# lambda_bl49.net
KiCad netlist of a schematic drawn in EAGLE
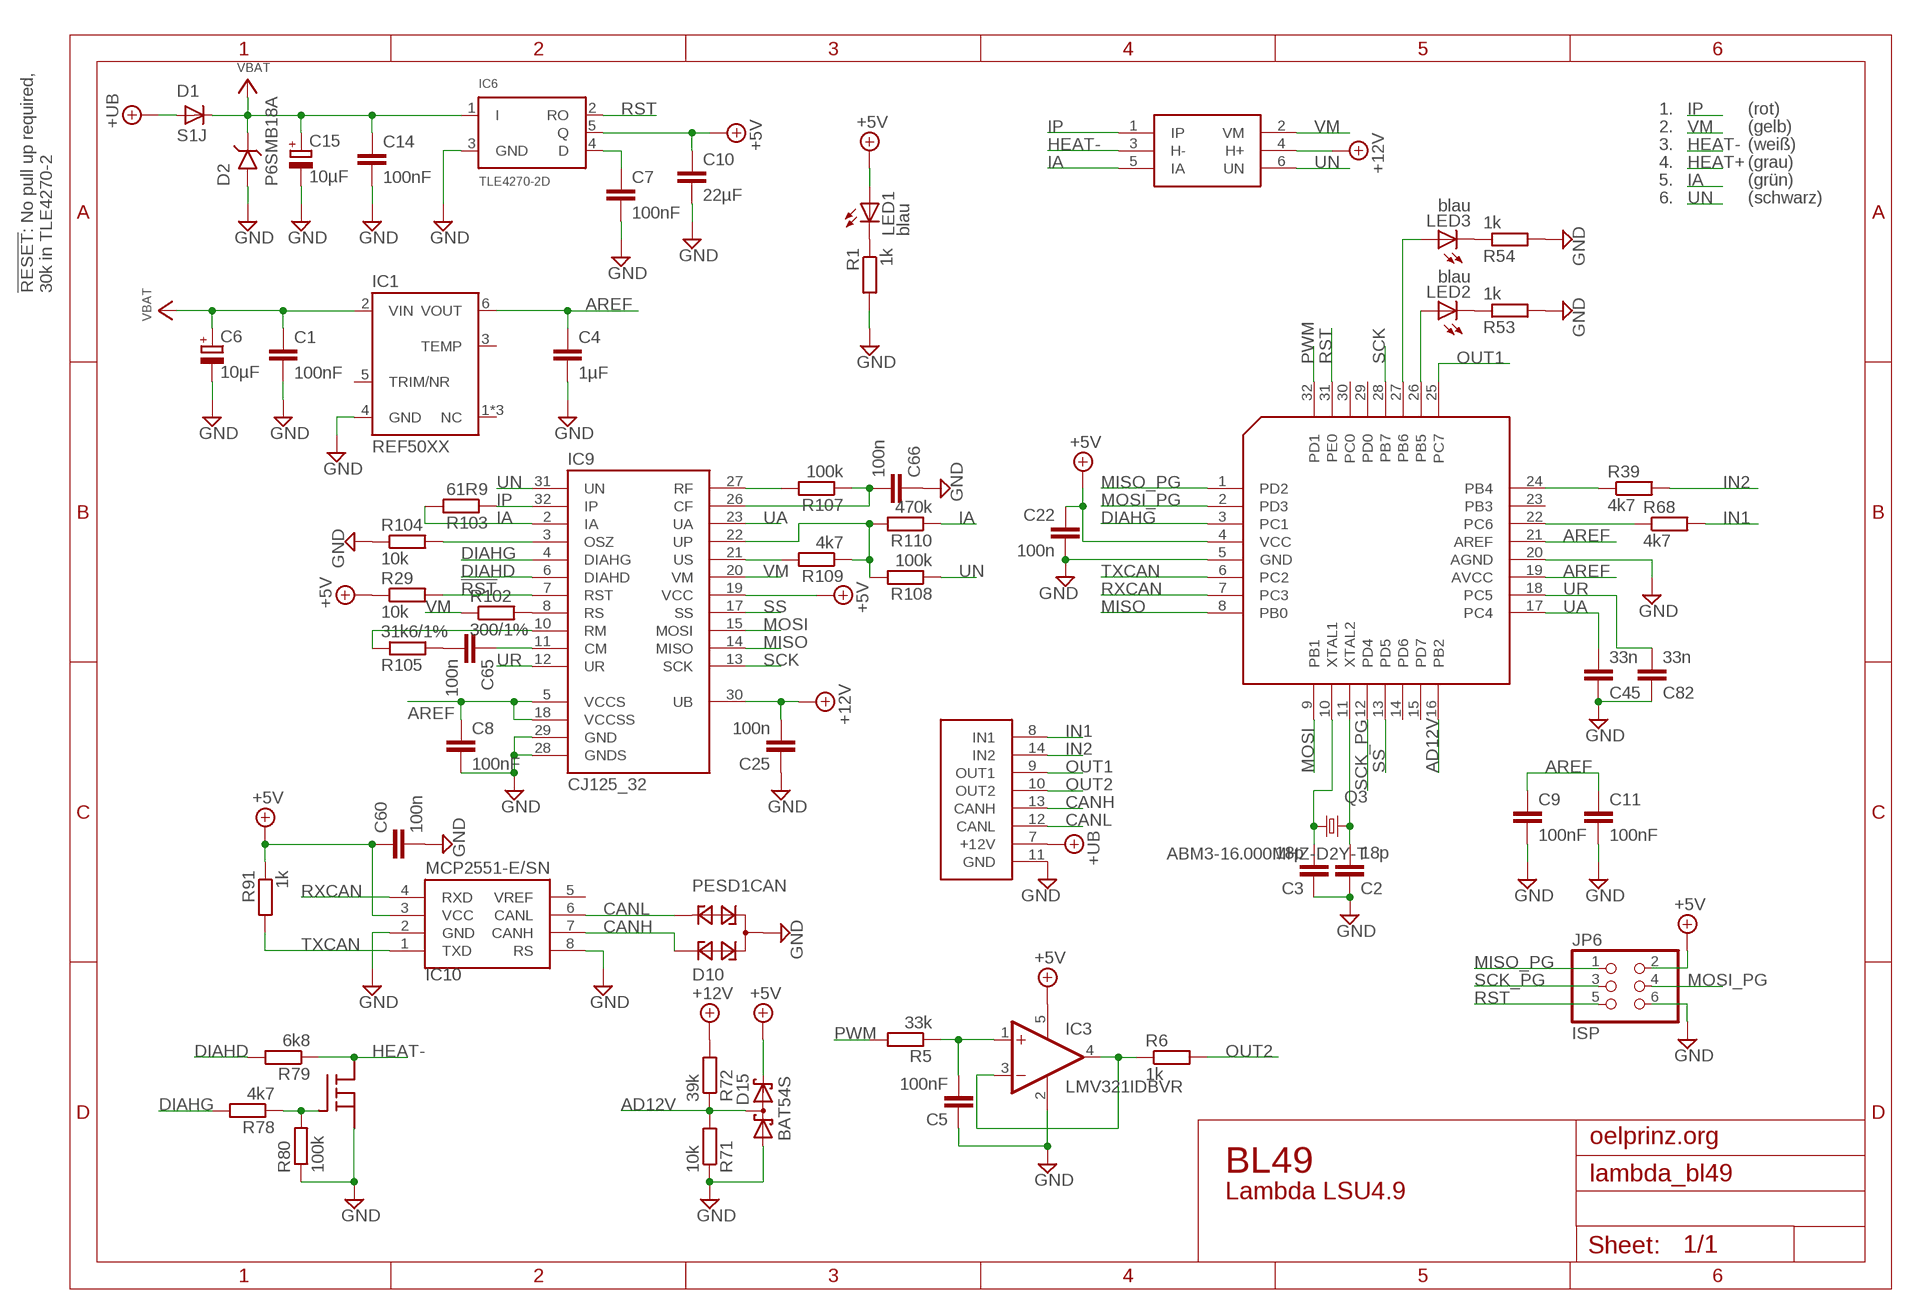
[diagram p0: schematic, sheet 1]

(export (version "E")
  (design (tool "Eeschema 10.0.6"))
  (components
    (comp (ref "C1")
      (value "100nF")
      (footprint "eagle-import:C0603")
      (libsource (lib "eagle-import") (part "rcl_334_C-EUC0603"))
    )
    (comp (ref "C2")
      (value "18p")
      (footprint "eagle-import:C0603")
      (libsource (lib "eagle-import") (part "C-EUC0603"))
    )
    (comp (ref "C3")
      (value "18p")
      (footprint "eagle-import:C0603")
      (libsource (lib "eagle-import") (part "C-EUC0603"))
    )
    (comp (ref "C4")
      (value "1µF")
      (footprint "eagle-import:C0603")
      (libsource (lib "eagle-import") (part "rcl_334_C-EUC0603"))
    )
    (comp (ref "C5")
      (value "100nF")
      (footprint "eagle-import:C0603")
      (libsource (lib "eagle-import") (part "C-EUC0603"))
    )
    (comp (ref "C6")
      (value "10µF")
      (footprint "eagle-import:PANASONIC_D")
      (libsource (lib "eagle-import") (part "CPOL-EUD"))
    )
    (comp (ref "C7")
      (value "100nF")
      (footprint "eagle-import:C0603")
      (libsource (lib "eagle-import") (part "rcl_334_C-EUC0603"))
    )
    (comp (ref "C8")
      (value "100nF")
      (footprint "eagle-import:C0603")
      (libsource (lib "eagle-import") (part "rcl_334_C-EUC0603"))
    )
    (comp (ref "C9")
      (value "100nF")
      (footprint "eagle-import:C0603")
      (libsource (lib "eagle-import") (part "rcl_334_C-EUC0603"))
    )
    (comp (ref "C10")
      (value "22µF")
      (footprint "eagle-import:C1206")
      (libsource (lib "eagle-import") (part "rcl_334_C-EUC1206"))
    )
    (comp (ref "C11")
      (value "100nF")
      (footprint "eagle-import:C0603")
      (libsource (lib "eagle-import") (part "rcl_334_C-EUC0603"))
    )
    (comp (ref "C14")
      (value "100nF")
      (footprint "eagle-import:C0603")
      (libsource (lib "eagle-import") (part "rcl_334_C-EUC0603"))
    )
    (comp (ref "C15")
      (value "10µF")
      (footprint "eagle-import:PANASONIC_D")
      (libsource (lib "eagle-import") (part "CPOL-EUD"))
    )
    (comp (ref "C22")
      (value "100n")
      (footprint "eagle-import:C0603")
      (libsource (lib "eagle-import") (part "C-EUC0603"))
    )
    (comp (ref "C25")
      (value "100n")
      (footprint "eagle-import:C0603")
      (libsource (lib "eagle-import") (part "rcl_334_C-EUC0603"))
    )
    (comp (ref "C45")
      (value "33n")
      (footprint "eagle-import:C0603")
      (libsource (lib "eagle-import") (part "C-EUC0603"))
    )
    (comp (ref "C60")
      (value "100n")
      (footprint "eagle-import:C0603")
      (libsource (lib "eagle-import") (part "C-EUC0603"))
    )
    (comp (ref "C65")
      (value "100n")
      (footprint "eagle-import:C0603")
      (libsource (lib "eagle-import") (part "C-EUC0603"))
    )
    (comp (ref "C66")
      (value "100n")
      (footprint "eagle-import:C0603")
      (libsource (lib "eagle-import") (part "C-EUC0603"))
    )
    (comp (ref "C82")
      (value "33n")
      (footprint "eagle-import:C0603")
      (libsource (lib "eagle-import") (part "C-EUC0603"))
    )
    (comp (ref "D1")
      (value "S1J")
      (footprint "eagle-import:SMADIODE")
      (libsource (lib "eagle-import") (part "DIODESMA"))
    )
    (comp (ref "D2")
      (value "P6SMB18A")
      (footprint "eagle-import:DO-214AA")
      (libsource (lib "eagle-import") (part "P6SMBXXASMB"))
    )
    (comp (ref "D10")
      (value "PESD1CAN")
      (footprint "eagle-import:SOT23")
      (libsource (lib "eagle-import") (part "PESD1CAN"))
    )
    (comp (ref "D15")
      (value "BAT54S")
      (footprint "eagle-import:SOT23")
      (libsource (lib "eagle-import") (part "BAT54S"))
    )
    (comp (ref "IC1")
      (value "REF50XX")
      (footprint "eagle-import:SOIC127P600X175-8N")
      (fields
        (field (name "MANUFACTURER_PART_NUMBER") "REF5050AIDR")
        (field (name "MOUSER_PART_NUMBER") "595-REF5050AIDR")
      )
      (libsource (lib "eagle-import") (part "REF50XX"))
    )
    (comp (ref "IC3")
      (value "LMV321IDBVR")
      (footprint "eagle-import:SC70-5L")
      (libsource (lib "eagle-import") (part "LMV321?M7"))
    )
    (comp (ref "IC6")
      (value "TLE4270-2D")
      (footprint "eagle-import:TO252-51")
      (libsource (lib "eagle-import") (part "TLE4270-2D"))
    )
    (comp (ref "IC9")
      (value "CJ125_32")
      (footprint "eagle-import:TQFP32-08")
      (libsource (lib "eagle-import") (part "CJ125_32"))
    )
    (comp (ref "IC10")
      (value "MCP2551-E/SN")
      (footprint "eagle-import:SOIC8")
      (libsource (lib "eagle-import") (part "MCP255"))
    )
    (comp (ref "JP6")
      (value "ISP")
      (footprint "eagle-import:2X03")
      (libsource (lib "eagle-import") (part "PINHD-2X3"))
    )
    (comp (ref "LED1")
      (value "blau")
      (footprint "eagle-import:SML0805")
      (libsource (lib "eagle-import") (part "LEDSML0805"))
    )
    (comp (ref "LED2")
      (value "blau")
      (footprint "eagle-import:SML0805")
      (libsource (lib "eagle-import") (part "LEDSML0805"))
    )
    (comp (ref "LED3")
      (value "blau")
      (footprint "eagle-import:SML0805")
      (libsource (lib "eagle-import") (part "LEDSML0805"))
    )
    (comp (ref "Q3")
      (value "ABM3-16.000MHZ-D2Y-T")
      (footprint "eagle-import:ABM3")
      (libsource (lib "eagle-import") (part "ABM3-8.000MHZ-D2Y-T"))
    )
    (comp (ref "R1")
      (value "1k")
      (footprint "eagle-import:R0603")
      (libsource (lib "eagle-import") (part "R-EU_R0603"))
    )
    (comp (ref "R5")
      (value "33k")
      (footprint "eagle-import:R0603")
      (libsource (lib "eagle-import") (part "R-EU_R0603"))
    )
    (comp (ref "R6")
      (value "1k")
      (footprint "eagle-import:R0603")
      (libsource (lib "eagle-import") (part "R-EU_R0603"))
    )
    (comp (ref "R29")
      (value "10k")
      (footprint "eagle-import:R0603")
      (libsource (lib "eagle-import") (part "R-EU_R0603"))
    )
    (comp (ref "R39")
      (value "4k7")
      (footprint "eagle-import:R0603")
      (libsource (lib "eagle-import") (part "R-EU_R0603"))
    )
    (comp (ref "R53")
      (value "1k")
      (footprint "eagle-import:R0603")
      (libsource (lib "eagle-import") (part "R-EU_R0603"))
    )
    (comp (ref "R54")
      (value "1k")
      (footprint "eagle-import:R0603")
      (libsource (lib "eagle-import") (part "R-EU_R0603"))
    )
    (comp (ref "R68")
      (value "4k7")
      (footprint "eagle-import:R0603")
      (libsource (lib "eagle-import") (part "R-EU_R0603"))
    )
    (comp (ref "R71")
      (value "10k")
      (footprint "eagle-import:R0603")
      (libsource (lib "eagle-import") (part "R-EU_R0603"))
    )
    (comp (ref "R72")
      (value "39k")
      (footprint "eagle-import:R0603")
      (libsource (lib "eagle-import") (part "R-EU_R0603"))
    )
    (comp (ref "R78")
      (value "4k7")
      (footprint "eagle-import:R0603")
      (libsource (lib "eagle-import") (part "R-EU_R0603"))
    )
    (comp (ref "R79")
      (value "6k8")
      (footprint "eagle-import:R0603")
      (libsource (lib "eagle-import") (part "R-EU_R0603"))
    )
    (comp (ref "R80")
      (value "100k")
      (footprint "eagle-import:R0603")
      (libsource (lib "eagle-import") (part "R-EU_R0603"))
    )
    (comp (ref "R91")
      (value "1k")
      (footprint "eagle-import:R0603")
      (libsource (lib "eagle-import") (part "R-EU_R0603"))
    )
    (comp (ref "R102")
      (value "300/1%")
      (footprint "eagle-import:R0603")
      (libsource (lib "eagle-import") (part "R-EU_R0603"))
    )
    (comp (ref "R103")
      (value "61R9")
      (footprint "eagle-import:R0603")
      (libsource (lib "eagle-import") (part "R-EU_R0603"))
    )
    (comp (ref "R104")
      (value "10k")
      (footprint "eagle-import:R0603")
      (libsource (lib "eagle-import") (part "R-EU_R0603"))
    )
    (comp (ref "R105")
      (value "31k6/1%")
      (footprint "eagle-import:R0603")
      (libsource (lib "eagle-import") (part "R-EU_R0603"))
    )
    (comp (ref "R107")
      (value "100k")
      (footprint "eagle-import:R0603")
      (libsource (lib "eagle-import") (part "R-EU_R0603"))
    )
    (comp (ref "R108")
      (value "100k")
      (footprint "eagle-import:R0603")
      (libsource (lib "eagle-import") (part "R-EU_R0603"))
    )
    (comp (ref "R109")
      (value "4k7")
      (footprint "eagle-import:R0603")
      (libsource (lib "eagle-import") (part "R-EU_R0603"))
    )
    (comp (ref "R110")
      (value "470k")
      (footprint "eagle-import:R0603")
      (libsource (lib "eagle-import") (part "R-EU_R0603"))
    )
    (comp (ref "U$1")
      (value "BL49")
      (footprint "eagle-import:BL49")
      (libsource (lib "eagle-import") (part "BL49"))
    )
    (comp (ref "U$2")
      (value "ATMEGA32M1-AU")
      (footprint "eagle-import:TQFP32-08")
      (libsource (lib "eagle-import") (part "AT32M1"))
    )
    (comp (ref "U$3")
      (value "STD30NF06LT4")
      (footprint "eagle-import:DPACK_2")
      (libsource (lib "eagle-import") (part "IRLZ44"))
    )
  )
  (nets
    (net (code "1") (name "+5V") (class "Default")
      (node (ref "C10") (pin "1") (pinfunction "1_1") (pintype "passive"))
      (node (ref "C22") (pin "1") (pinfunction "1_1") (pintype "passive"))
      (node (ref "C60") (pin "1") (pinfunction "1_1") (pintype "passive"))
      (node (ref "D15") (pin "2") (pinfunction "C2_2") (pintype "passive"))
      (node (ref "IC10") (pin "3") (pinfunction "VCC_3") (pintype "bidirectional"))
      (node (ref "IC3") (pin "5") (pinfunction "V+_5") (pintype "power_in"))
      (node (ref "IC6") (pin "5") (pinfunction "Q_5") (pintype "bidirectional"))
      (node (ref "IC9") (pin "19") (pinfunction "VCC_19") (pintype "bidirectional"))
      (node (ref "JP6") (pin "2") (pinfunction "2_2") (pintype "passive"))
      (node (ref "LED1") (pin "A") (pinfunction "A_A") (pintype "passive"))
      (node (ref "R29") (pin "1") (pinfunction "1_1") (pintype "passive"))
      (node (ref "R91") (pin "1") (pinfunction "1_1") (pintype "passive"))
      (node (ref "U$2") (pin "4") (pinfunction "VCC_4") (pintype "bidirectional"))
    )
    (net (code "2") (name "+12V") (class "Default")
      (node (ref "C25") (pin "2") (pinfunction "2_2") (pintype "passive"))
      (node (ref "IC9") (pin "30") (pinfunction "UB_30") (pintype "bidirectional"))
      (node (ref "R72") (pin "2") (pinfunction "2_2") (pintype "passive"))
      (node (ref "U$1") (pin "4") (pinfunction "H+_4") (pintype "bidirectional"))
    )
    (net (code "3") (name "+UB") (class "Default")
      (node (ref "D1") (pin "A") (pinfunction "A_A") (pintype "passive"))
      (node (ref "U$1") (pin "7") (pinfunction "+12V_7") (pintype "bidirectional"))
    )
    (net (code "4") (name "/AD12V") (class "Default")
      (node (ref "D15") (pin "3") (pinfunction "C1A2_3") (pintype "passive"))
      (node (ref "R71") (pin "2") (pinfunction "2_2") (pintype "passive"))
      (node (ref "R72") (pin "1") (pinfunction "1_1") (pintype "passive"))
      (node (ref "U$2") (pin "16") (pinfunction "PB2_16") (pintype "bidirectional"))
    )
    (net (code "5") (name "/AREF") (class "Default")
      (node (ref "C11") (pin "1") (pinfunction "1_1") (pintype "passive"))
      (node (ref "C4") (pin "1") (pinfunction "1_1") (pintype "passive"))
      (node (ref "C8") (pin "1") (pinfunction "1_1") (pintype "passive"))
      (node (ref "C9") (pin "1") (pinfunction "1_1") (pintype "passive"))
      (node (ref "IC1") (pin "6") (pinfunction "VOUT_6") (pintype "output"))
      (node (ref "IC9") (pin "18") (pinfunction "VCCSS_18") (pintype "bidirectional"))
      (node (ref "IC9") (pin "5") (pinfunction "VCCS_5") (pintype "bidirectional"))
      (node (ref "U$2") (pin "19") (pinfunction "AVCC_19") (pintype "bidirectional"))
      (node (ref "U$2") (pin "21") (pinfunction "AREF_21") (pintype "bidirectional"))
    )
    (net (code "6") (name "/CANH") (class "Default")
      (node (ref "D10") (pin "1") (pinfunction "1_1") (pintype "passive"))
      (node (ref "IC10") (pin "7") (pinfunction "CANH_7") (pintype "bidirectional"))
      (node (ref "U$1") (pin "13") (pinfunction "CANH_13") (pintype "bidirectional"))
    )
    (net (code "7") (name "/CANL") (class "Default")
      (node (ref "D10") (pin "2") (pinfunction "2_2") (pintype "passive"))
      (node (ref "IC10") (pin "6") (pinfunction "CANL_6") (pintype "bidirectional"))
      (node (ref "U$1") (pin "12") (pinfunction "CANL_12") (pintype "bidirectional"))
    )
    (net (code "8") (name "/DIAHD") (class "Default")
      (node (ref "IC9") (pin "6") (pinfunction "DIAHD_6") (pintype "bidirectional"))
      (node (ref "R79") (pin "2") (pinfunction "2_2") (pintype "passive"))
    )
    (net (code "9") (name "/DIAHG") (class "Default")
      (node (ref "IC9") (pin "4") (pinfunction "DIAHG_4") (pintype "bidirectional"))
      (node (ref "R78") (pin "2") (pinfunction "2_2") (pintype "passive"))
      (node (ref "U$2") (pin "3") (pinfunction "PC1_3") (pintype "bidirectional"))
    )
    (net (code "11") (name "/HEAT-") (class "Default")
      (node (ref "R79") (pin "1") (pinfunction "1_1") (pintype "passive"))
      (node (ref "U$1") (pin "3") (pinfunction "H-_3") (pintype "bidirectional"))
      (node (ref "U$3") (pin "D") (pinfunction "2_D") (pintype "bidirectional"))
    )
    (net (code "12") (name "/IA") (class "Default")
      (node (ref "IC9") (pin "2") (pinfunction "IA_2") (pintype "bidirectional"))
      (node (ref "R103") (pin "2") (pinfunction "2_2") (pintype "passive"))
      (node (ref "R110") (pin "1") (pinfunction "1_1") (pintype "passive"))
      (node (ref "U$1") (pin "5") (pinfunction "IA_5") (pintype "bidirectional"))
    )
    (net (code "13") (name "/IN1") (class "Default")
      (node (ref "R68") (pin "2") (pinfunction "2_2") (pintype "passive"))
      (node (ref "U$1") (pin "8") (pinfunction "IN1_8") (pintype "bidirectional"))
    )
    (net (code "14") (name "/IN2") (class "Default")
      (node (ref "R39") (pin "2") (pinfunction "2_2") (pintype "passive"))
      (node (ref "U$1") (pin "14") (pinfunction "IN2_14") (pintype "bidirectional"))
    )
    (net (code "15") (name "/IP") (class "Default")
      (node (ref "IC9") (pin "32") (pinfunction "IP_32") (pintype "bidirectional"))
      (node (ref "R103") (pin "1") (pinfunction "1_1") (pintype "passive"))
      (node (ref "U$1") (pin "1") (pinfunction "IP_1") (pintype "bidirectional"))
    )
    (net (code "16") (name "/MISO") (class "Default")
      (node (ref "IC9") (pin "14") (pinfunction "MISO_14") (pintype "bidirectional"))
      (node (ref "U$2") (pin "8") (pinfunction "PB0_8") (pintype "bidirectional"))
    )
    (net (code "17") (name "/MISO_PG") (class "Default")
      (node (ref "JP6") (pin "1") (pinfunction "1_1") (pintype "passive"))
      (node (ref "U$2") (pin "1") (pinfunction "PD2_1") (pintype "bidirectional"))
    )
    (net (code "18") (name "/MOSI") (class "Default")
      (node (ref "IC9") (pin "15") (pinfunction "MOSI_15") (pintype "bidirectional"))
      (node (ref "U$2") (pin "9") (pinfunction "PB1_9") (pintype "bidirectional"))
    )
    (net (code "19") (name "/MOSI_PG") (class "Default")
      (node (ref "JP6") (pin "4") (pinfunction "4_4") (pintype "passive"))
      (node (ref "U$2") (pin "2") (pinfunction "PD3_2") (pintype "bidirectional"))
    )
    (net (code "20") (name "/OUT1") (class "Default")
      (node (ref "U$1") (pin "9") (pinfunction "OUT1_9") (pintype "bidirectional"))
      (node (ref "U$2") (pin "25") (pinfunction "PC7_25") (pintype "bidirectional"))
    )
    (net (code "21") (name "/OUT2") (class "Default")
      (node (ref "R6") (pin "2") (pinfunction "2_2") (pintype "passive"))
      (node (ref "U$1") (pin "10") (pinfunction "OUT2_10") (pintype "bidirectional"))
    )
    (net (code "22") (name "/PWM") (class "Default")
      (node (ref "R5") (pin "2") (pinfunction "2_2") (pintype "passive"))
      (node (ref "U$2") (pin "32") (pinfunction "PD1_32") (pintype "bidirectional"))
    )
    (net (code "23") (name "/RST") (class "Default")
      (node (ref "IC6") (pin "2") (pinfunction "RO_2") (pintype "bidirectional"))
      (node (ref "JP6") (pin "5") (pinfunction "5_5") (pintype "passive"))
      (node (ref "U$2") (pin "31") (pinfunction "PE0_31") (pintype "bidirectional"))
    )
    (net (code "24") (name "/RXCAN") (class "Default")
      (node (ref "IC10") (pin "4") (pinfunction "RXD_4") (pintype "bidirectional"))
      (node (ref "U$2") (pin "7") (pinfunction "PC3_7") (pintype "bidirectional"))
    )
    (net (code "25") (name "/SCK") (class "Default")
      (node (ref "IC9") (pin "13") (pinfunction "SCK_13") (pintype "bidirectional"))
      (node (ref "U$2") (pin "28") (pinfunction "PB7_28") (pintype "bidirectional"))
    )
    (net (code "26") (name "/SCK_PG") (class "Default")
      (node (ref "JP6") (pin "3") (pinfunction "3_3") (pintype "passive"))
      (node (ref "U$2") (pin "12") (pinfunction "PD4_12") (pintype "bidirectional"))
    )
    (net (code "27") (name "/SS") (class "Default")
      (node (ref "IC9") (pin "17") (pinfunction "SS_17") (pintype "bidirectional"))
      (node (ref "U$2") (pin "13") (pinfunction "PD5_13") (pintype "bidirectional"))
    )
    (net (code "28") (name "/TXCAN") (class "Default")
      (node (ref "IC10") (pin "1") (pinfunction "TXD_1") (pintype "bidirectional"))
      (node (ref "R91") (pin "2") (pinfunction "2_2") (pintype "passive"))
      (node (ref "U$2") (pin "6") (pinfunction "PC2_6") (pintype "bidirectional"))
    )
    (net (code "29") (name "/UA") (class "Default")
      (node (ref "C45") (pin "2") (pinfunction "2_2") (pintype "passive"))
      (node (ref "IC9") (pin "23") (pinfunction "UA_23") (pintype "bidirectional"))
      (node (ref "U$2") (pin "17") (pinfunction "PC4_17") (pintype "bidirectional"))
    )
    (net (code "30") (name "/UN") (class "Default")
      (node (ref "IC9") (pin "31") (pinfunction "UN_31") (pintype "bidirectional"))
      (node (ref "R108") (pin "1") (pinfunction "1_1") (pintype "passive"))
      (node (ref "U$1") (pin "6") (pinfunction "UN_6") (pintype "bidirectional"))
    )
    (net (code "31") (name "/UR") (class "Default")
      (node (ref "C82") (pin "2") (pinfunction "2_2") (pintype "passive"))
      (node (ref "IC9") (pin "12") (pinfunction "UR_12") (pintype "bidirectional"))
      (node (ref "U$2") (pin "18") (pinfunction "PC5_18") (pintype "bidirectional"))
    )
    (net (code "32") (name "/VM") (class "Default")
      (node (ref "IC9") (pin "20") (pinfunction "VM_20") (pintype "bidirectional"))
      (node (ref "R102") (pin "1") (pinfunction "1_1") (pintype "passive"))
      (node (ref "U$1") (pin "2") (pinfunction "VM_2") (pintype "bidirectional"))
    )
    (net (code "33") (name "/~{RST}") (class "Default")
      (node (ref "IC9") (pin "7") (pinfunction "RST_7") (pintype "bidirectional"))
      (node (ref "R29") (pin "2") (pinfunction "2_2") (pintype "passive"))
    )
    (net (code "34") (name "GND") (class "Default")
      (node (ref "C1") (pin "2") (pinfunction "2_2") (pintype "passive"))
      (node (ref "C10") (pin "2") (pinfunction "2_2") (pintype "passive"))
      (node (ref "C11") (pin "2") (pinfunction "2_2") (pintype "passive"))
      (node (ref "C14") (pin "2") (pinfunction "2_2") (pintype "passive"))
      (node (ref "C15") (pin "-") (pinfunction "-_-") (pintype "passive"))
      (node (ref "C2") (pin "1") (pinfunction "1_1") (pintype "passive"))
      (node (ref "C22") (pin "2") (pinfunction "2_2") (pintype "passive"))
      (node (ref "C25") (pin "1") (pinfunction "1_1") (pintype "passive"))
      (node (ref "C3") (pin "1") (pinfunction "1_1") (pintype "passive"))
      (node (ref "C4") (pin "2") (pinfunction "2_2") (pintype "passive"))
      (node (ref "C45") (pin "1") (pinfunction "1_1") (pintype "passive"))
      (node (ref "C5") (pin "1") (pinfunction "1_1") (pintype "passive"))
      (node (ref "C6") (pin "-") (pinfunction "-_-") (pintype "passive"))
      (node (ref "C60") (pin "2") (pinfunction "2_2") (pintype "passive"))
      (node (ref "C66") (pin "1") (pinfunction "1_1") (pintype "passive"))
      (node (ref "C7") (pin "2") (pinfunction "2_2") (pintype "passive"))
      (node (ref "C8") (pin "2") (pinfunction "2_2") (pintype "passive"))
      (node (ref "C82") (pin "1") (pinfunction "1_1") (pintype "passive"))
      (node (ref "C9") (pin "2") (pinfunction "2_2") (pintype "passive"))
      (node (ref "D10") (pin "3") (pinfunction "3_3") (pintype "passive"))
      (node (ref "D15") (pin "1") (pinfunction "A1_1") (pintype "passive"))
      (node (ref "D2") (pin "P$2") (pinfunction "A_P$2") (pintype "passive"))
      (node (ref "IC1") (pin "4") (pinfunction "GND_4") (pintype "power_in"))
      (node (ref "IC10") (pin "2") (pinfunction "GND_2") (pintype "bidirectional"))
      (node (ref "IC10") (pin "8") (pinfunction "RS_8") (pintype "bidirectional"))
      (node (ref "IC3") (pin "2") (pinfunction "V-_2") (pintype "power_in"))
      (node (ref "IC6") (pin "3") (pinfunction "GND_3") (pintype "bidirectional"))
      (node (ref "IC9") (pin "28") (pinfunction "GNDS_28") (pintype "bidirectional"))
      (node (ref "IC9") (pin "29") (pinfunction "GND_29") (pintype "bidirectional"))
      (node (ref "JP6") (pin "6") (pinfunction "6_6") (pintype "passive"))
      (node (ref "R1") (pin "2") (pinfunction "2_2") (pintype "passive"))
      (node (ref "R104") (pin "1") (pinfunction "1_1") (pintype "passive"))
      (node (ref "R53") (pin "2") (pinfunction "2_2") (pintype "passive"))
      (node (ref "R54") (pin "2") (pinfunction "2_2") (pintype "passive"))
      (node (ref "R71") (pin "1") (pinfunction "1_1") (pintype "passive"))
      (node (ref "R80") (pin "1") (pinfunction "1_1") (pintype "passive"))
      (node (ref "U$1") (pin "11") (pinfunction "GND_11") (pintype "bidirectional"))
      (node (ref "U$2") (pin "20") (pinfunction "AGND_20") (pintype "bidirectional"))
      (node (ref "U$2") (pin "5") (pinfunction "GND_5") (pintype "bidirectional"))
      (node (ref "U$3") (pin "S") (pinfunction "3_S") (pintype "bidirectional"))
    )
    (net (code "35") (name "Net-(C65-Pad2)") (class "Default")
      (node (ref "C65") (pin "2") (pinfunction "2_2") (pintype "passive"))
      (node (ref "R105") (pin "2") (pinfunction "2_2") (pintype "passive"))
    )
    (net (code "36") (name "Net-(IC3-+IN)") (class "Default")
      (node (ref "C5") (pin "2") (pinfunction "2_2") (pintype "passive"))
      (node (ref "IC3") (pin "1") (pinfunction "+IN_1") (pintype "input"))
      (node (ref "R5") (pin "1") (pinfunction "1_1") (pintype "passive"))
    )
    (net (code "37") (name "Net-(IC3--IN)") (class "Default")
      (node (ref "IC3") (pin "3") (pinfunction "-IN_3") (pintype "input"))
      (node (ref "IC3") (pin "4") (pinfunction "OUT_4") (pintype "output"))
      (node (ref "R6") (pin "1") (pinfunction "1_1") (pintype "passive"))
    )
    (net (code "38") (name "Net-(IC6-D)") (class "Default")
      (node (ref "C7") (pin "1") (pinfunction "1_1") (pintype "passive"))
      (node (ref "IC6") (pin "4") (pinfunction "D_4") (pintype "bidirectional"))
    )
    (net (code "39") (name "Net-(IC9-CF)") (class "Default")
      (node (ref "C66") (pin "2") (pinfunction "2_2") (pintype "passive"))
      (node (ref "IC9") (pin "26") (pinfunction "CF_26") (pintype "bidirectional"))
      (node (ref "R107") (pin "1") (pinfunction "1_1") (pintype "passive"))
    )
    (net (code "40") (name "Net-(IC9-CM)") (class "Default")
      (node (ref "C65") (pin "1") (pinfunction "1_1") (pintype "passive"))
      (node (ref "IC9") (pin "11") (pinfunction "CM_11") (pintype "bidirectional"))
    )
    (net (code "41") (name "Net-(IC9-OSZ)") (class "Default")
      (node (ref "IC9") (pin "3") (pinfunction "OSZ_3") (pintype "bidirectional"))
      (node (ref "R104") (pin "2") (pinfunction "2_2") (pintype "passive"))
    )
    (net (code "42") (name "Net-(IC9-RF)") (class "Default")
      (node (ref "IC9") (pin "27") (pinfunction "RF_27") (pintype "bidirectional"))
      (node (ref "R107") (pin "2") (pinfunction "2_2") (pintype "passive"))
    )
    (net (code "43") (name "Net-(IC9-RM)") (class "Default")
      (node (ref "IC9") (pin "10") (pinfunction "RM_10") (pintype "bidirectional"))
      (node (ref "R105") (pin "1") (pinfunction "1_1") (pintype "passive"))
    )
    (net (code "44") (name "Net-(IC9-RS)") (class "Default")
      (node (ref "IC9") (pin "8") (pinfunction "RS_8") (pintype "bidirectional"))
      (node (ref "R102") (pin "2") (pinfunction "2_2") (pintype "passive"))
    )
    (net (code "45") (name "Net-(IC9-UP)") (class "Default")
      (node (ref "IC9") (pin "22") (pinfunction "UP_22") (pintype "bidirectional"))
      (node (ref "R108") (pin "2") (pinfunction "2_2") (pintype "passive"))
      (node (ref "R109") (pin "1") (pinfunction "1_1") (pintype "passive"))
      (node (ref "R110") (pin "2") (pinfunction "2_2") (pintype "passive"))
    )
    (net (code "46") (name "Net-(IC9-US)") (class "Default")
      (node (ref "IC9") (pin "21") (pinfunction "US_21") (pintype "bidirectional"))
      (node (ref "R109") (pin "2") (pinfunction "2_2") (pintype "passive"))
    )
    (net (code "47") (name "Net-(LED1-PadC)") (class "Default")
      (node (ref "LED1") (pin "C") (pinfunction "C_C") (pintype "passive"))
      (node (ref "R1") (pin "1") (pinfunction "1_1") (pintype "passive"))
    )
    (net (code "48") (name "Net-(LED2-PadC)") (class "Default")
      (node (ref "LED2") (pin "C") (pinfunction "C_C") (pintype "passive"))
      (node (ref "R53") (pin "1") (pinfunction "1_1") (pintype "passive"))
    )
    (net (code "49") (name "Net-(LED3-PadC)") (class "Default")
      (node (ref "LED3") (pin "C") (pinfunction "C_C") (pintype "passive"))
      (node (ref "R54") (pin "1") (pinfunction "1_1") (pintype "passive"))
    )
    (net (code "50") (name "Net-(U$2-PB4)") (class "Default")
      (node (ref "R39") (pin "1") (pinfunction "1_1") (pintype "passive"))
      (node (ref "U$2") (pin "24") (pinfunction "PB4_24") (pintype "bidirectional"))
    )
    (net (code "51") (name "Net-(U$2-PB5)") (class "Default")
      (node (ref "LED2") (pin "A") (pinfunction "A_A") (pintype "passive"))
      (node (ref "U$2") (pin "26") (pinfunction "PB5_26") (pintype "bidirectional"))
    )
    (net (code "52") (name "Net-(U$2-PB6)") (class "Default")
      (node (ref "LED3") (pin "A") (pinfunction "A_A") (pintype "passive"))
      (node (ref "U$2") (pin "27") (pinfunction "PB6_27") (pintype "bidirectional"))
    )
    (net (code "53") (name "Net-(U$2-PC6)") (class "Default")
      (node (ref "R68") (pin "1") (pinfunction "1_1") (pintype "passive"))
      (node (ref "U$2") (pin "22") (pinfunction "PC6_22") (pintype "bidirectional"))
    )
    (net (code "54") (name "Net-(U$2-XTAL1)") (class "Default")
      (node (ref "C3") (pin "2") (pinfunction "2_2") (pintype "passive"))
      (node (ref "Q3") (pin "2") (pinfunction "2_2") (pintype "bidirectional"))
      (node (ref "U$2") (pin "10") (pinfunction "XTAL1_10") (pintype "bidirectional"))
    )
    (net (code "55") (name "Net-(U$2-XTAL2)") (class "Default")
      (node (ref "C2") (pin "2") (pinfunction "2_2") (pintype "passive"))
      (node (ref "Q3") (pin "1") (pinfunction "1_1") (pintype "bidirectional"))
      (node (ref "U$2") (pin "11") (pinfunction "XTAL2_11") (pintype "bidirectional"))
    )
    (net (code "56") (name "Net-(U$3-1)") (class "Default")
      (node (ref "R78") (pin "1") (pinfunction "1_1") (pintype "passive"))
      (node (ref "R80") (pin "2") (pinfunction "2_2") (pintype "passive"))
      (node (ref "U$3") (pin "G") (pinfunction "1_G") (pintype "bidirectional"))
    )
    (net (code "57") (name "VBAT") (class "Default")
      (node (ref "C1") (pin "1") (pinfunction "1_1") (pintype "passive"))
      (node (ref "C14") (pin "1") (pinfunction "1_1") (pintype "passive"))
      (node (ref "C15") (pin "+") (pinfunction "+_+") (pintype "passive"))
      (node (ref "C6") (pin "+") (pinfunction "+_+") (pintype "passive"))
      (node (ref "D1") (pin "C") (pinfunction "C_C") (pintype "passive"))
      (node (ref "D2") (pin "P$1") (pinfunction "C_P$1") (pintype "passive"))
      (node (ref "IC1") (pin "2") (pinfunction "VIN_2") (pintype "power_in"))
      (node (ref "IC6") (pin "1") (pinfunction "I_1") (pintype "bidirectional"))
    )
    (net (code "58") (name "unconnected-(IC1-NC-Pad1)") (class "Default")
      (node (ref "IC1") (pin "1") (pinfunction "NC_1") (pintype "no_connect"))
    )
    (net (code "59") (name "unconnected-(IC1-NC-Pad7)") (class "Default")
      (node (ref "IC1") (pin "7") (pinfunction "NC_7") (pintype "no_connect"))
    )
    (net (code "60") (name "unconnected-(IC1-NC-Pad8)") (class "Default")
      (node (ref "IC1") (pin "8") (pinfunction "NC_8") (pintype "no_connect"))
    )
    (net (code "61") (name "unconnected-(IC1-TEMP-Pad3)") (class "Default")
      (node (ref "IC1") (pin "3") (pinfunction "TEMP_3") (pintype "input"))
    )
    (net (code "62") (name "unconnected-(IC1-TRIM{slash}NR-Pad5)") (class "Default")
      (node (ref "IC1") (pin "5") (pinfunction "TRIM/NR_5") (pintype "input"))
    )
    (net (code "63") (name "unconnected-(IC10-VREF-Pad5)") (class "Default")
      (node (ref "IC10") (pin "5") (pinfunction "VREF_5") (pintype "bidirectional"))
    )
    (net (code "64") (name "unconnected-(U$2-PB3-Pad23)") (class "Default")
      (node (ref "U$2") (pin "23") (pinfunction "PB3_23") (pintype "bidirectional"))
    )
    (net (code "65") (name "unconnected-(U$2-PC0-Pad30)") (class "Default")
      (node (ref "U$2") (pin "30") (pinfunction "PC0_30") (pintype "bidirectional"))
    )
    (net (code "66") (name "unconnected-(U$2-PD0-Pad29)") (class "Default")
      (node (ref "U$2") (pin "29") (pinfunction "PD0_29") (pintype "bidirectional"))
    )
    (net (code "67") (name "unconnected-(U$2-PD6-Pad14)") (class "Default")
      (node (ref "U$2") (pin "14") (pinfunction "PD6_14") (pintype "bidirectional"))
    )
    (net (code "68") (name "unconnected-(U$2-PD7-Pad15)") (class "Default")
      (node (ref "U$2") (pin "15") (pinfunction "PD7_15") (pintype "bidirectional"))
    )
  )
)
